# GSM_Signal_Control.net
KiCad netlist of a schematic drawn in Altium Designer
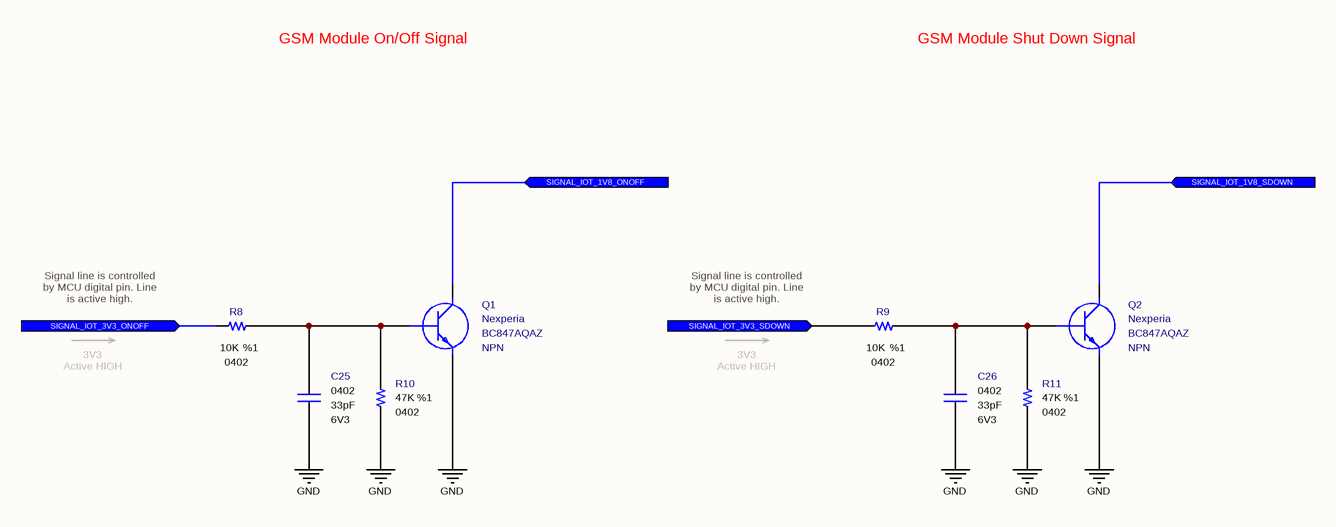
[diagram p0: GSM Signal Control.SchDoc]

(export (version "E")
  (design (tool "Eeschema 10.0.6"))
  (components
    (comp (ref "C25")
      (value "33pF")
      (footprint "CAPACITOR_0402")
      (description "Capacitor - 33pF [0402] (Ceramic)")
      (fields
        (field (name "CASE") "0402")
        (field (name "TOLERANCE") "10%")
        (field (name "VOLTAGE") "6V3")
        (field (name "MANUFACTURER PART NUMBER") "C0402C330J9RACAUTO")
      )
      (libsource (lib "Ovoo_Library") (part "Capacitor - 33pF [0402-6V3]"))
    )
    (comp (ref "C26")
      (value "33pF")
      (footprint "CAPACITOR_0402")
      (description "Capacitor - 33pF [0402] (Ceramic)")
      (fields
        (field (name "CASE") "0402")
        (field (name "TOLERANCE") "10%")
        (field (name "VOLTAGE") "6V3")
        (field (name "MANUFACTURER PART NUMBER") "C0402C330J9RACAUTO")
      )
      (libsource (lib "Ovoo_Library") (part "Capacitor - 33pF [0402-6V3]"))
    )
    (comp (ref "Q1")
      (value "BC847AQAZ")
      (footprint "SOT1215")
      (description "Bipolar NPN Transistors")
      (fields
        (field (name "POLARITY") "NPN")
        (field (name "MANUFACTURER NAME") "Nexperia")
        (field (name "MANUFACTURER PART NUMBER") "BC847AQAZ")
      )
      (libsource (lib "Ovoo_Library") (part "Transistor - BC847"))
    )
    (comp (ref "Q2")
      (value "BC847AQAZ")
      (footprint "SOT1215")
      (description "Bipolar NPN Transistors")
      (fields
        (field (name "POLARITY") "NPN")
        (field (name "MANUFACTURER NAME") "Nexperia")
        (field (name "MANUFACTURER PART NUMBER") "BC847AQAZ")
      )
      (libsource (lib "Ovoo_Library") (part "Transistor - BC847"))
    )
    (comp (ref "R8")
      (value "10K")
      (footprint "RESISTOR_0402")
      (description "Thick Film Resistors - SMD 1/16 W 10 Kohms 1%")
      (fields
        (field (name "TOLERANCE") "%1")
        (field (name "CASE") "0402")
        (field (name "MANUFACTURER PART NUMBER") "CRCW040210K0FKED")
        (field (name "MOUSER PART NUMBER") "71-CRCW0402-10K-E3")
      )
      (libsource (lib "Ovoo_Library") (part "Resistor - 10K"))
    )
    (comp (ref "R9")
      (value "10K")
      (footprint "RESISTOR_0402")
      (description "Thick Film Resistors - SMD 1/16 W 10 Kohms 1%")
      (fields
        (field (name "TOLERANCE") "%1")
        (field (name "CASE") "0402")
        (field (name "MANUFACTURER PART NUMBER") "CRCW040210K0FKED")
        (field (name "MOUSER PART NUMBER") "71-CRCW0402-10K-E3")
      )
      (libsource (lib "Ovoo_Library") (part "Resistor - 10K"))
    )
    (comp (ref "R10")
      (value "47K")
      (footprint "RESISTOR_0402")
      (description "Thick Film Resistors - SMD 1/16 W 47 Kohms 1%")
      (fields
        (field (name "TOLERANCE") "%1")
        (field (name "CASE") "0402")
        (field (name "MANUFACTURER PART NUMBER") "CRCW040247K0FKED")
        (field (name "Comment") "47K - 0402 - %1 - 1/16W")
      )
      (libsource (lib "Ovoo_Library") (part "Resistor - 47K"))
    )
    (comp (ref "R11")
      (value "47K")
      (footprint "RESISTOR_0402")
      (description "Thick Film Resistors - SMD 1/16 W 47 Kohms 1%")
      (fields
        (field (name "TOLERANCE") "%1")
        (field (name "CASE") "0402")
        (field (name "MANUFACTURER PART NUMBER") "CRCW040247K0FKED")
        (field (name "Comment") "47K - 0402 - %1 - 1/16W")
      )
      (libsource (lib "Ovoo_Library") (part "Resistor - 47K"))
    )
  )
  (nets
    (net (code "1") (name "/SIGNAL_IOT_1V8_ONOFF") (class "Default")
      (node (ref "Q1") (pin "3") (pinfunction "C_3") (pintype "passive"))
    )
    (net (code "2") (name "/SIGNAL_IOT_1V8_SDOWN") (class "Default")
      (node (ref "Q2") (pin "3") (pinfunction "C_3") (pintype "passive"))
    )
    (net (code "3") (name "/SIGNAL_IOT_3V3_ONOFF") (class "Default")
      (node (ref "R8") (pin "2") (pinfunction "2_2") (pintype "passive"))
    )
    (net (code "4") (name "/SIGNAL_IOT_3V3_SDOWN") (class "Default")
      (node (ref "R9") (pin "2") (pinfunction "2_2") (pintype "passive"))
    )
    (net (code "5") (name "GND") (class "Default")
      (node (ref "C25") (pin "2") (pinfunction "2_2") (pintype "passive"))
      (node (ref "C26") (pin "2") (pinfunction "2_2") (pintype "passive"))
      (node (ref "Q1") (pin "2") (pinfunction "E_2") (pintype "passive"))
      (node (ref "Q2") (pin "2") (pinfunction "E_2") (pintype "passive"))
      (node (ref "R10") (pin "1") (pinfunction "1_1") (pintype "passive"))
      (node (ref "R11") (pin "1") (pinfunction "1_1") (pintype "passive"))
    )
    (net (code "6") (name "Net-(Q1-B)") (class "Default")
      (node (ref "C25") (pin "1") (pinfunction "1_1") (pintype "passive"))
      (node (ref "Q1") (pin "1") (pinfunction "B_1") (pintype "passive"))
      (node (ref "R10") (pin "2") (pinfunction "2_2") (pintype "passive"))
      (node (ref "R8") (pin "1") (pinfunction "1_1") (pintype "passive"))
    )
    (net (code "7") (name "Net-(Q2-B)") (class "Default")
      (node (ref "C26") (pin "1") (pinfunction "1_1") (pintype "passive"))
      (node (ref "Q2") (pin "1") (pinfunction "B_1") (pintype "passive"))
      (node (ref "R11") (pin "2") (pinfunction "2_2") (pintype "passive"))
      (node (ref "R9") (pin "1") (pinfunction "1_1") (pintype "passive"))
    )
  )
)
